# fpc_1.net
KiCad netlist of a schematic drawn in Altium Designer
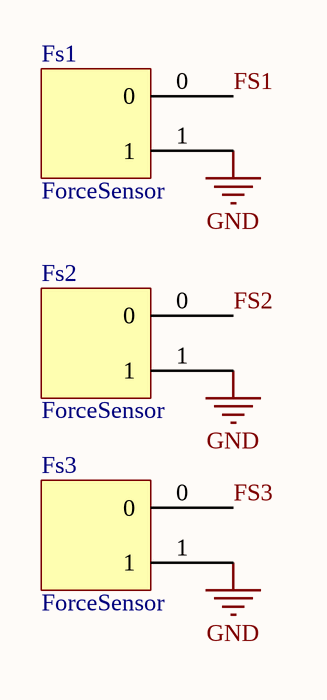
[diagram p0: fpc_1.SchDoc]

(export (version "E")
  (design (tool "Eeschema 10.0.6"))
  (components
    (comp (ref "Fs1")
      (value "ForceSensor")
      (footprint "sensor_connector")
      (libsource (lib "force_sensor_lib") (part "ForceSensor"))
    )
    (comp (ref "Fs2")
      (value "ForceSensor")
      (footprint "sensor_connector")
      (libsource (lib "force_sensor_lib") (part "ForceSensor"))
    )
    (comp (ref "Fs3")
      (value "ForceSensor")
      (footprint "sensor_connector")
      (libsource (lib "force_sensor_lib") (part "ForceSensor"))
    )
  )
  (nets
    (net (code "1") (name "/FS1") (class "Default")
      (node (ref "Fs1") (pin "0") (pinfunction "0_0") (pintype "passive"))
    )
    (net (code "2") (name "/FS2") (class "Default")
      (node (ref "Fs2") (pin "0") (pinfunction "0_0") (pintype "passive"))
    )
    (net (code "3") (name "/FS3") (class "Default")
      (node (ref "Fs3") (pin "0") (pinfunction "0_0") (pintype "passive"))
    )
    (net (code "4") (name "GND") (class "Default")
      (node (ref "Fs1") (pin "1") (pinfunction "1_1") (pintype "passive"))
      (node (ref "Fs2") (pin "1") (pinfunction "1_1") (pintype "passive"))
      (node (ref "Fs3") (pin "1") (pinfunction "1_1") (pintype "passive"))
    )
  )
)
